# uTrakHF.net
KiCad netlist of a schematic drawn in EAGLE
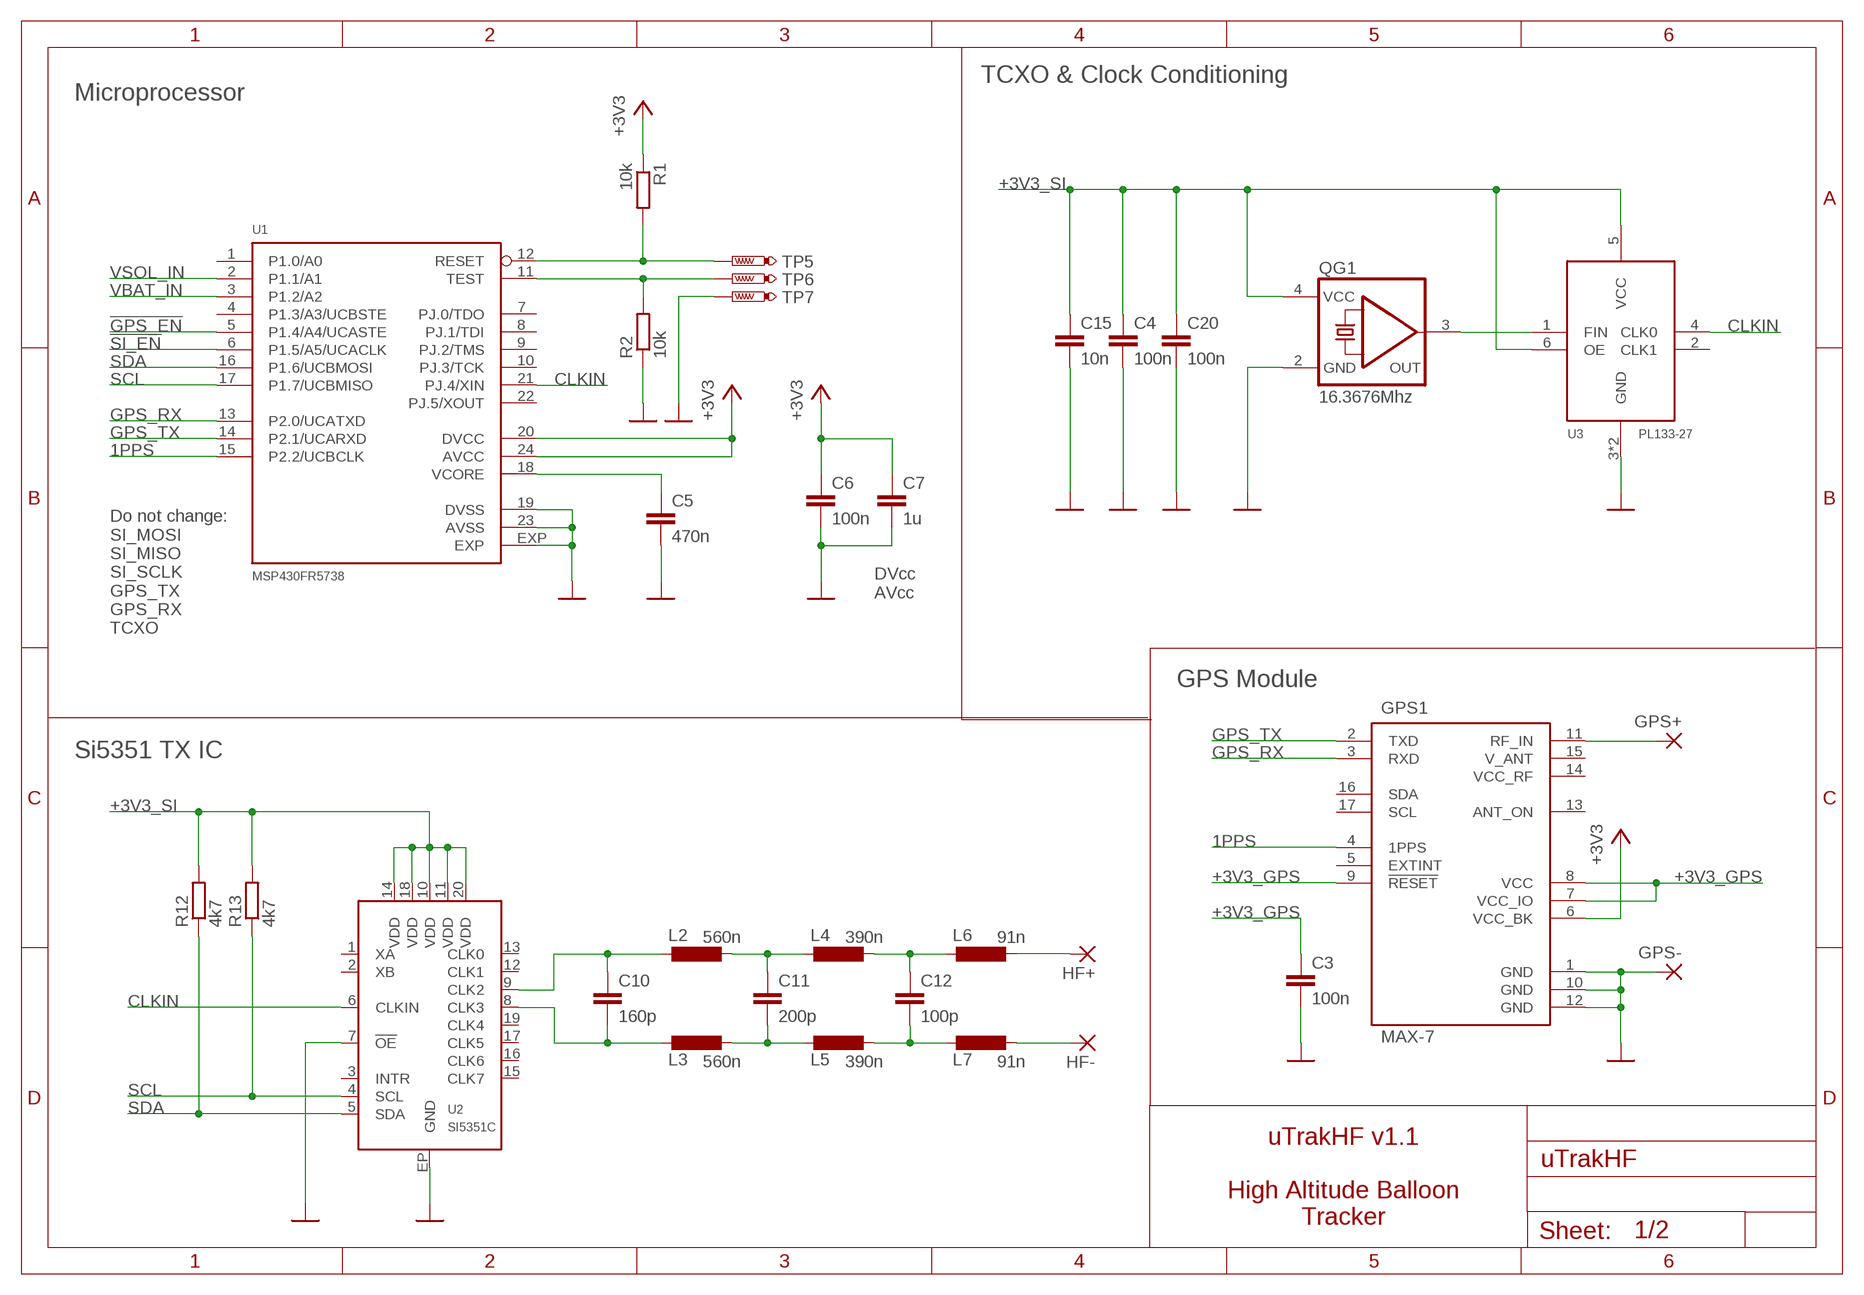
[diagram p0: schematic, sheet 1]
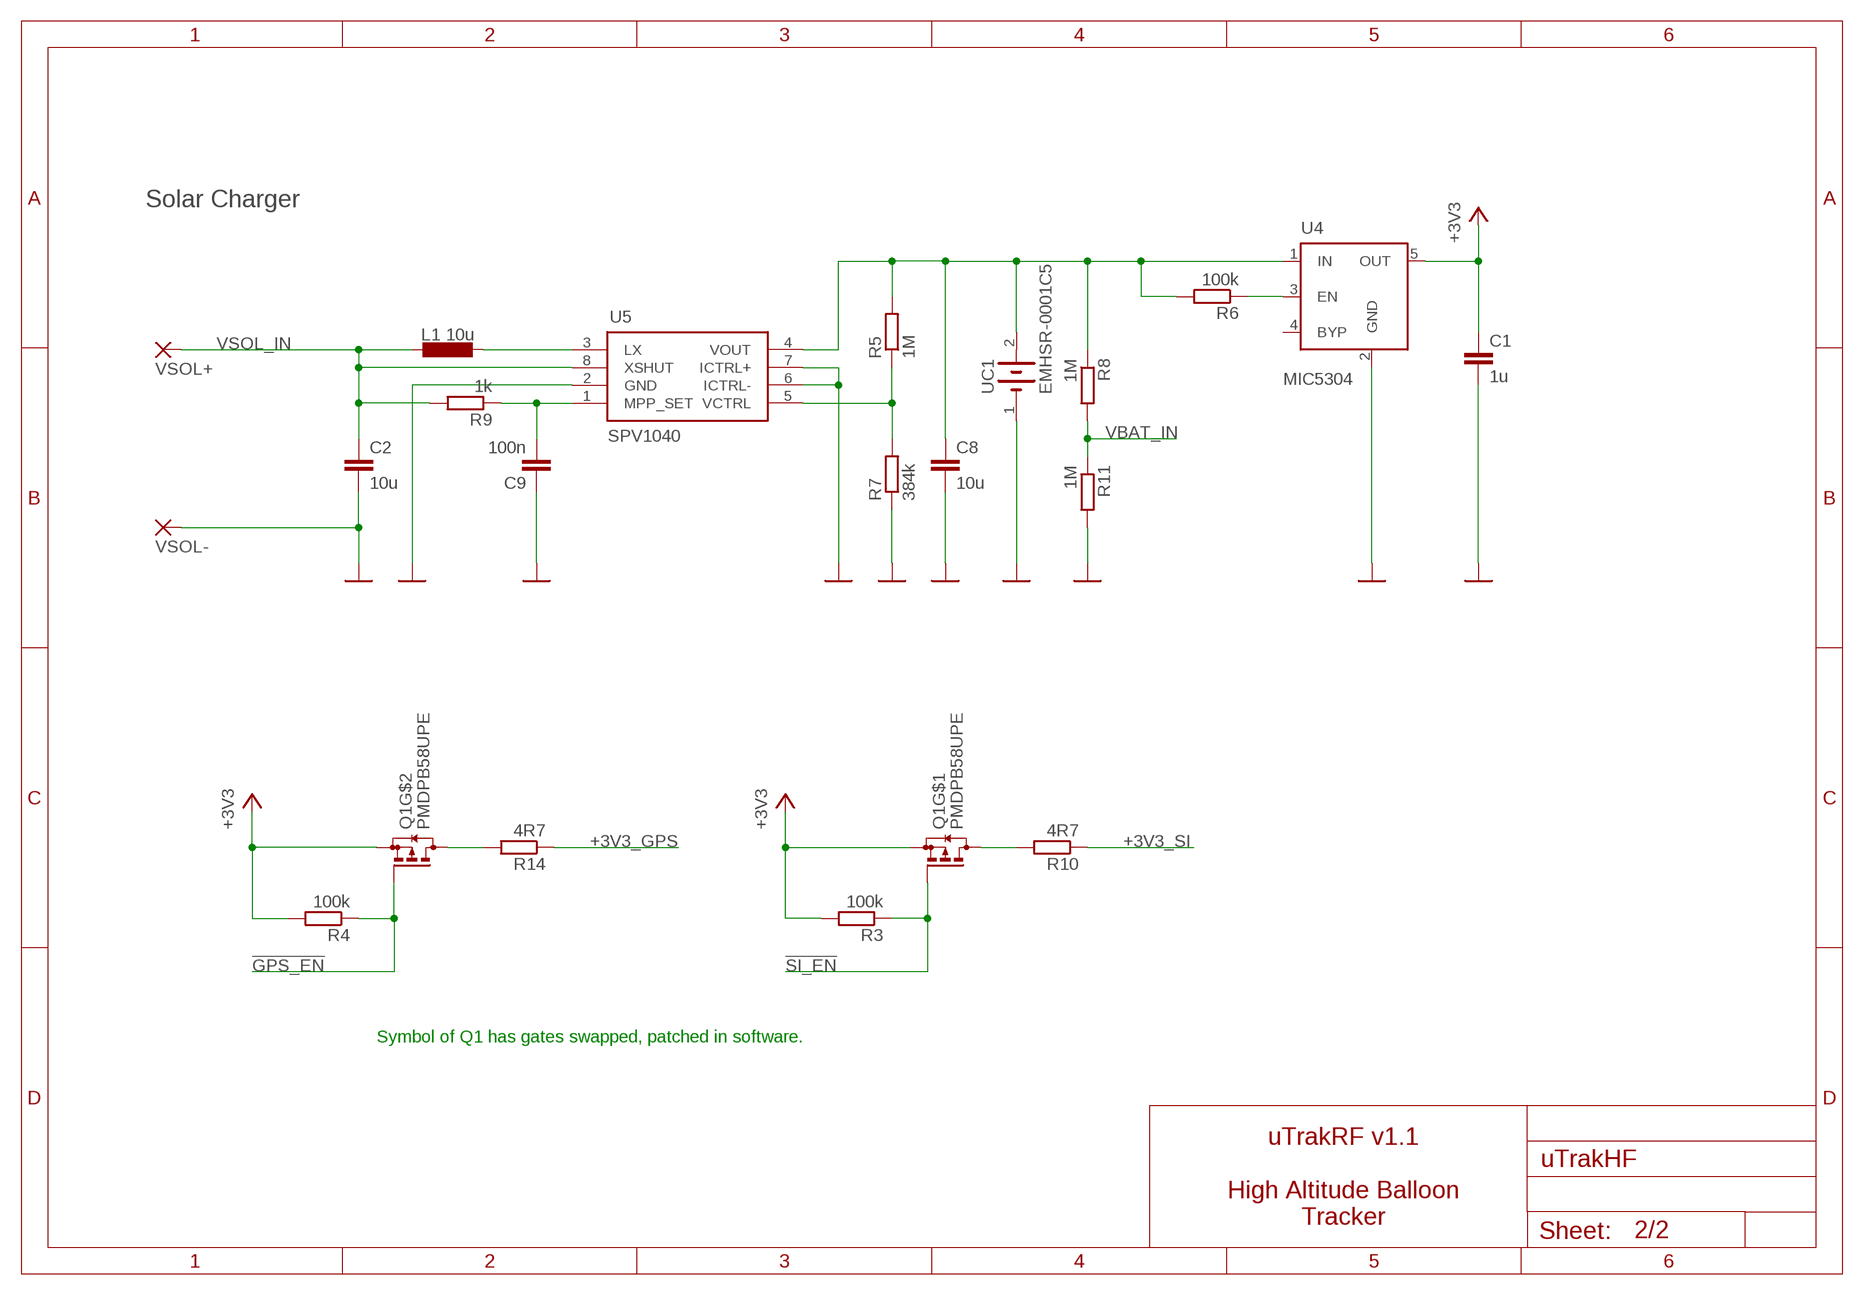
[diagram p1: schematic, sheet 2]

(export (version "E")
  (design (tool "Eeschema 10.0.6"))
  (components
    (comp (ref "C1")
      (value "1u")
      (footprint "eagle-import:C0603")
      (libsource (lib "eagle-import") (part "C-EUC0603"))
    )
    (comp (ref "C2")
      (value "10u")
      (footprint "eagle-import:C0603")
      (libsource (lib "eagle-import") (part "C-EUC0603"))
    )
    (comp (ref "C8")
      (value "10u")
      (footprint "eagle-import:C0603")
      (libsource (lib "eagle-import") (part "C-EUC0603"))
    )
    (comp (ref "C9")
      (value "100n")
      (footprint "eagle-import:C0402")
      (libsource (lib "eagle-import") (part "C-EUC0402"))
    )
    (comp (ref "L1")
      (value "10u")
      (footprint "eagle-import:LPS4018")
      (fields (field (name "PARTNO") "994-LPS4018-223MRB"))
      (libsource (lib "eagle-import") (part "LPS4018"))
    )
    (comp (ref "Q1")
      (value "PMDPB58UPE")
      (footprint "eagle-import:SOT1118")
      (fields (field (name "PARTNO") "771-PMDPB58UPE,115"))
      (libsource (lib "eagle-import") (part "PMDPB58UPE"))
    )
    (comp (ref "R3")
      (value "100k")
      (footprint "eagle-import:R0402")
      (fields (field (name "PARTNO") "603-RC0402FR-07100KL"))
      (libsource (lib "eagle-import") (part "R-EU_R0402"))
    )
    (comp (ref "R4")
      (value "100k")
      (footprint "eagle-import:R0402")
      (fields (field (name "PARTNO") "603-RC0402FR-07100KL"))
      (libsource (lib "eagle-import") (part "R-EU_R0402"))
    )
    (comp (ref "R5")
      (value "1M")
      (footprint "eagle-import:R0402")
      (libsource (lib "eagle-import") (part "R-EU_R0402"))
    )
    (comp (ref "R6")
      (value "100k")
      (footprint "eagle-import:R0402")
      (libsource (lib "eagle-import") (part "R-EU_R0402"))
    )
    (comp (ref "R7")
      (value "384k")
      (footprint "eagle-import:R0402")
      (libsource (lib "eagle-import") (part "R-EU_R0402"))
    )
    (comp (ref "R8")
      (value "1M")
      (footprint "eagle-import:R0402")
      (fields (field (name "PARTNO") "603-RC0402FR-071ML"))
      (libsource (lib "eagle-import") (part "R-EU_R0402"))
    )
    (comp (ref "R9")
      (value "1k")
      (footprint "eagle-import:R0402")
      (libsource (lib "eagle-import") (part "R-EU_R0402"))
    )
    (comp (ref "R10")
      (value "4R7")
      (footprint "eagle-import:R0402")
      (fields (field (name "PARTNO") "603-RC0402FR-07100KL"))
      (libsource (lib "eagle-import") (part "R-EU_R0402"))
    )
    (comp (ref "R11")
      (value "1M")
      (footprint "eagle-import:R0402")
      (fields (field (name "PARTNO") "603-RC0402FR-071ML"))
      (libsource (lib "eagle-import") (part "R-EU_R0402"))
    )
    (comp (ref "R14")
      (value "4R7")
      (footprint "eagle-import:R0402")
      (fields (field (name "PARTNO") "603-RC0402FR-07100KL"))
      (libsource (lib "eagle-import") (part "R-EU_R0402"))
    )
    (comp (ref "U4")
      (value "MIC5304")
      (footprint "eagle-import:SOT23-5")
      (libsource (lib "eagle-import") (part "MIC5219XX"))
    )
    (comp (ref "U5")
      (value "SPV1040")
      (footprint "eagle-import:TSSOP8")
      (libsource (lib "eagle-import") (part "SPV1040"))
    )
    (comp (ref "UC1")
      (value "EMHSR-0001C5")
      (footprint "eagle-import:EMHSR-0001C5-005R0")
      (fields (field (name "PARTNO") "581-SCMR22C155MRBA0"))
      (libsource (lib "eagle-import") (part "EMHSR-0001C5"))
    )
    (comp (ref "VSOL+")
      (value "SMD2")
      (footprint "eagle-import:SMD1,27-2,54")
      (libsource (lib "eagle-import") (part "SMD2"))
    )
    (comp (ref "VSOL-")
      (value "SMD2")
      (footprint "eagle-import:SMD1,27-2,54")
      (libsource (lib "eagle-import") (part "SMD2"))
    )
    (comp (ref "C3")
      (value "100n")
      (footprint "eagle-import:C0402")
      (fields (field (name "PARTNO") "81-GRM155R71C104KA88"))
      (libsource (lib "eagle-import") (part "C-EUC0402"))
    )
    (comp (ref "C4")
      (value "100n")
      (footprint "eagle-import:C0402")
      (fields (field (name "PARTNO") "81-GRM155R71C104KA88"))
      (libsource (lib "eagle-import") (part "C-EUC0402"))
    )
    (comp (ref "C5")
      (value "470n")
      (footprint "eagle-import:C0603")
      (fields (field (name "PARTNO") "81-GCM188R71C474KA5D"))
      (libsource (lib "eagle-import") (part "C-EUC0603"))
    )
    (comp (ref "C6")
      (value "100n")
      (footprint "eagle-import:C0402")
      (fields (field (name "PARTNO") "81-GRM155R71C104KA88"))
      (libsource (lib "eagle-import") (part "C-EUC0402"))
    )
    (comp (ref "C7")
      (value "1u")
      (footprint "eagle-import:C0603")
      (fields (field (name "PARTNO") "81-GRM39R105K10"))
      (libsource (lib "eagle-import") (part "C-EUC0603"))
    )
    (comp (ref "C10")
      (value "160p")
      (footprint "eagle-import:C0402")
      (fields (field (name "PARTNO") "81-GRM1555C1H161JA01"))
      (libsource (lib "eagle-import") (part "C-EUC0402"))
    )
    (comp (ref "C11")
      (value "200p")
      (footprint "eagle-import:C0402")
      (fields (field (name "PARTNO") "81-GRM1555C1H201JA1D"))
      (libsource (lib "eagle-import") (part "C-EUC0402"))
    )
    (comp (ref "C12")
      (value "100p")
      (footprint "eagle-import:C0402")
      (fields (field (name "PARTNO") "81-GRM1555C1H101JA1D"))
      (libsource (lib "eagle-import") (part "C-EUC0402"))
    )
    (comp (ref "C15")
      (value "10n")
      (footprint "eagle-import:C0402")
      (fields (field (name "PARTNO") "81-GRM155R71H103MA8D"))
      (libsource (lib "eagle-import") (part "C-EUC0402"))
    )
    (comp (ref "C20")
      (value "100n")
      (footprint "eagle-import:C0402")
      (fields (field (name "PARTNO") "81-GRM155R71C104KA88"))
      (libsource (lib "eagle-import") (part "C-EUC0402"))
    )
    (comp (ref "GPS+")
      (value "SMD2")
      (footprint "eagle-import:SMD1,27-2,54")
      (libsource (lib "eagle-import") (part "SMD2"))
    )
    (comp (ref "GPS-")
      (value "SMD2")
      (footprint "eagle-import:SMD1,27-2,54")
      (libsource (lib "eagle-import") (part "SMD2"))
    )
    (comp (ref "GPS1")
      (value "MAX-7")
      (footprint "eagle-import:UBLOX-7")
      (libsource (lib "eagle-import") (part "MAX-7"))
    )
    (comp (ref "HF+")
      (value "SMD2")
      (footprint "eagle-import:SMD1,27-2,54")
      (libsource (lib "eagle-import") (part "SMD2"))
    )
    (comp (ref "HF-")
      (value "SMD2")
      (footprint "eagle-import:SMD1,27-2,54")
      (libsource (lib "eagle-import") (part "SMD2"))
    )
    (comp (ref "L2")
      (value "560n")
      (footprint "eagle-import:C0603")
      (fields (field (name "PARTNO") "810-MLJ1608WR56JT000"))
      (libsource (lib "eagle-import") (part "L0603"))
    )
    (comp (ref "L3")
      (value "560n")
      (footprint "eagle-import:C0603")
      (fields (field (name "PARTNO") "810-MLJ1608WR56JT000"))
      (libsource (lib "eagle-import") (part "L0603"))
    )
    (comp (ref "L4")
      (value "390n")
      (footprint "eagle-import:C0603")
      (fields (field (name "PARTNO") "810-MLJ1608WR39JT000"))
      (libsource (lib "eagle-import") (part "L0603"))
    )
    (comp (ref "L5")
      (value "390n")
      (footprint "eagle-import:C0603")
      (fields (field (name "PARTNO") "810-MLJ1608WR39JT000"))
      (libsource (lib "eagle-import") (part "L0603"))
    )
    (comp (ref "L6")
      (value "91n")
      (footprint "eagle-import:C0603")
      (fields (field (name "PARTNO") "81-LQW18AN91NG00D"))
      (libsource (lib "eagle-import") (part "L0603"))
    )
    (comp (ref "L7")
      (value "91n")
      (footprint "eagle-import:C0603")
      (fields (field (name "PARTNO") "81-LQW18AN91NG00D"))
      (libsource (lib "eagle-import") (part "L0603"))
    )
    (comp (ref "QG1")
      (value "16.3676Mhz")
      (footprint "eagle-import:CTS406")
      (libsource (lib "eagle-import") (part "XO"))
    )
    (comp (ref "R1")
      (value "10k")
      (footprint "eagle-import:R0402")
      (fields (field (name "PARTNO") "603-RC0402FR-0710KL"))
      (libsource (lib "eagle-import") (part "R-EU_R0402"))
    )
    (comp (ref "R2")
      (value "10k")
      (footprint "eagle-import:R0402")
      (fields (field (name "PARTNO") "603-RC0402FR-0710KL"))
      (libsource (lib "eagle-import") (part "R-EU_R0402"))
    )
    (comp (ref "R12")
      (value "4k7")
      (footprint "eagle-import:R0402")
      (fields (field (name "PARTNO") "603-RC0402FR-074K7L"))
      (libsource (lib "eagle-import") (part "R-EU_R0402"))
    )
    (comp (ref "R13")
      (value "4k7")
      (footprint "eagle-import:R0402")
      (fields (field (name "PARTNO") "603-RC0402FR-074K7L"))
      (libsource (lib "eagle-import") (part "R-EU_R0402"))
    )
    (comp (ref "TP5")
      (value "PTR1TP10SQ")
      (footprint "eagle-import:TP10SQ")
      (libsource (lib "eagle-import") (part "PTR1TP10SQ"))
    )
    (comp (ref "TP6")
      (value "PTR1TP10SQ")
      (footprint "eagle-import:TP10SQ")
      (libsource (lib "eagle-import") (part "PTR1TP10SQ"))
    )
    (comp (ref "TP7")
      (value "PTR1TP10SQ")
      (footprint "eagle-import:TP10SQ")
      (libsource (lib "eagle-import") (part "PTR1TP10SQ"))
    )
    (comp (ref "U1")
      (value "MSP430FR5738")
      (footprint "eagle-import:QFN24-4X4")
      (fields (field (name "PARTNO") "595-SP430FR5738IRGER"))
      (libsource (lib "eagle-import") (part "MSP430FR5738"))
    )
    (comp (ref "U2")
      (value "SI5351C")
      (footprint "eagle-import:QFN20-4X4")
      (fields (field (name "PARTNO") "634-SI5351C-B-GM"))
      (libsource (lib "eagle-import") (part "SI5351C"))
    )
    (comp (ref "U3")
      (value "PL133-27")
      (footprint "eagle-import:DFN6-2X3")
      (fields (field (name "PARTNO") "998-PL133-27GC-R"))
      (libsource (lib "eagle-import") (part "PL133-27"))
    )
  )
  (nets
    (net (code "1") (name "+3V3") (class "Default")
      (node (ref "C1") (pin "1") (pinfunction "1_1") (pintype "passive"))
      (node (ref "C6") (pin "1") (pinfunction "1_1") (pintype "passive"))
      (node (ref "C7") (pin "1") (pinfunction "1_1") (pintype "passive"))
      (node (ref "GPS1") (pin "6") (pinfunction "VCC_BK_6") (pintype "power_in"))
      (node (ref "Q1") (pin "1") (pinfunction "S_1") (pintype "passive"))
      (node (ref "Q1") (pin "4") (pinfunction "S_4") (pintype "passive"))
      (node (ref "R1") (pin "1") (pinfunction "1_1") (pintype "passive"))
      (node (ref "R3") (pin "2") (pinfunction "2_2") (pintype "passive"))
      (node (ref "R4") (pin "2") (pinfunction "2_2") (pintype "passive"))
      (node (ref "U1") (pin "20") (pinfunction "DVCC_20") (pintype "power_in"))
      (node (ref "U1") (pin "24") (pinfunction "AVCC_24") (pintype "power_in"))
      (node (ref "U4") (pin "5") (pinfunction "OUT_5") (pintype "output"))
    )
    (net (code "2") (name "+3V3_GPS") (class "Default")
      (node (ref "C3") (pin "1") (pinfunction "1_1") (pintype "passive"))
      (node (ref "GPS1") (pin "7") (pinfunction "VCC_IO_7") (pintype "power_in"))
      (node (ref "GPS1") (pin "8") (pinfunction "VCC_8") (pintype "power_in"))
      (node (ref "GPS1") (pin "9") (pinfunction "~{RESET}_9") (pintype "bidirectional"))
      (node (ref "R14") (pin "1") (pinfunction "1_1") (pintype "passive"))
    )
    (net (code "3") (name "+3V3_SI") (class "Default")
      (node (ref "C15") (pin "1") (pinfunction "1_1") (pintype "passive"))
      (node (ref "C20") (pin "1") (pinfunction "1_1") (pintype "passive"))
      (node (ref "C4") (pin "1") (pinfunction "1_1") (pintype "passive"))
      (node (ref "QG1") (pin "4") (pinfunction "VCC_4") (pintype "power_in"))
      (node (ref "R10") (pin "1") (pinfunction "1_1") (pintype "passive"))
      (node (ref "R12") (pin "2") (pinfunction "2_2") (pintype "passive"))
      (node (ref "R13") (pin "2") (pinfunction "2_2") (pintype "passive"))
      (node (ref "U2") (pin "10") (pinfunction "VDD_10") (pintype "bidirectional"))
      (node (ref "U2") (pin "11") (pinfunction "VDD_11") (pintype "bidirectional"))
      (node (ref "U2") (pin "14") (pinfunction "VDD_14") (pintype "bidirectional"))
      (node (ref "U2") (pin "18") (pinfunction "VDD_18") (pintype "bidirectional"))
      (node (ref "U2") (pin "20") (pinfunction "VDD_20") (pintype "bidirectional"))
      (node (ref "U3") (pin "5") (pinfunction "VCC_5") (pintype "power_in"))
      (node (ref "U3") (pin "6") (pinfunction "OE_6") (pintype "bidirectional"))
    )
    (net (code "4") (name "1PPS") (class "Default")
      (node (ref "GPS1") (pin "4") (pinfunction "1PPS_4") (pintype "bidirectional"))
      (node (ref "U1") (pin "15") (pinfunction "P2.2/UCBCLK_15") (pintype "bidirectional"))
    )
    (net (code "5") (name "CLKIN") (class "Default")
      (node (ref "U1") (pin "21") (pinfunction "PJ.4/XIN_21") (pintype "bidirectional"))
      (node (ref "U2") (pin "6") (pinfunction "CLKIN_6") (pintype "bidirectional"))
      (node (ref "U3") (pin "4") (pinfunction "CLK0_4") (pintype "bidirectional"))
    )
    (net (code "6") (name "GND") (class "Default")
      (node (ref "C1") (pin "2") (pinfunction "2_2") (pintype "passive"))
      (node (ref "C15") (pin "2") (pinfunction "2_2") (pintype "passive"))
      (node (ref "C2") (pin "2") (pinfunction "2_2") (pintype "passive"))
      (node (ref "C20") (pin "2") (pinfunction "2_2") (pintype "passive"))
      (node (ref "C3") (pin "2") (pinfunction "2_2") (pintype "passive"))
      (node (ref "C4") (pin "2") (pinfunction "2_2") (pintype "passive"))
      (node (ref "C5") (pin "2") (pinfunction "2_2") (pintype "passive"))
      (node (ref "C6") (pin "2") (pinfunction "2_2") (pintype "passive"))
      (node (ref "C7") (pin "2") (pinfunction "2_2") (pintype "passive"))
      (node (ref "C8") (pin "2") (pinfunction "2_2") (pintype "passive"))
      (node (ref "C9") (pin "1") (pinfunction "1_1") (pintype "passive"))
      (node (ref "GPS-") (pin "1") (pinfunction "P_1") (pintype "passive"))
      (node (ref "GPS1") (pin "1") (pinfunction "GND_1") (pintype "power_in"))
      (node (ref "GPS1") (pin "10") (pinfunction "GND_10") (pintype "power_in"))
      (node (ref "GPS1") (pin "12") (pinfunction "GND_12") (pintype "power_in"))
      (node (ref "QG1") (pin "2") (pinfunction "GND_2") (pintype "power_in"))
      (node (ref "R11") (pin "2") (pinfunction "2_2") (pintype "passive"))
      (node (ref "R2") (pin "1") (pinfunction "1_1") (pintype "passive"))
      (node (ref "R7") (pin "1") (pinfunction "1_1") (pintype "passive"))
      (node (ref "TP7") (pin "TP") (pinfunction "TP_TP") (pintype "input"))
      (node (ref "U1") (pin "19") (pinfunction "DVSS_19") (pintype "power_in"))
      (node (ref "U1") (pin "23") (pinfunction "AVSS_23") (pintype "power_in"))
      (node (ref "U1") (pin "EXP") (pinfunction "EXP_EXP") (pintype "power_in"))
      (node (ref "U2") (pin "7") (pinfunction "~{OE}_7") (pintype "bidirectional"))
      (node (ref "U2") (pin "EP") (pinfunction "GND_EP") (pintype "bidirectional"))
      (node (ref "U3") (pin "3") (pinfunction "GND_3") (pintype "power_in"))
      (node (ref "U3") (pin "EXP") (pinfunction "GND_EXP") (pintype "power_in"))
      (node (ref "U4") (pin "2") (pinfunction "GND_2") (pintype "power_in"))
      (node (ref "U5") (pin "2") (pinfunction "GND_2") (pintype "bidirectional"))
      (node (ref "U5") (pin "6") (pinfunction "ICTRL-_6") (pintype "bidirectional"))
      (node (ref "U5") (pin "7") (pinfunction "ICTRL+_7") (pintype "bidirectional"))
      (node (ref "UC1") (pin "1") (pinfunction "-_1") (pintype "passive"))
      (node (ref "VSOL-") (pin "1") (pinfunction "P_1") (pintype "passive"))
    )
    (net (code "7") (name "GPS_RX") (class "Default")
      (node (ref "GPS1") (pin "3") (pinfunction "RXD_3") (pintype "bidirectional"))
      (node (ref "U1") (pin "13") (pinfunction "P2.0/UCATXD_13") (pintype "bidirectional"))
    )
    (net (code "8") (name "GPS_TX") (class "Default")
      (node (ref "GPS1") (pin "2") (pinfunction "TXD_2") (pintype "bidirectional"))
      (node (ref "U1") (pin "14") (pinfunction "P2.1/UCARXD_14") (pintype "bidirectional"))
    )
    (net (code "9") (name "Net-(C11-Pad1)") (class "Default")
      (node (ref "C11") (pin "1") (pinfunction "1_1") (pintype "passive"))
      (node (ref "L2") (pin "2") (pinfunction "2_2") (pintype "passive"))
      (node (ref "L4") (pin "1") (pinfunction "1_1") (pintype "passive"))
    )
    (net (code "10") (name "Net-(C11-Pad2)") (class "Default")
      (node (ref "C11") (pin "2") (pinfunction "2_2") (pintype "passive"))
      (node (ref "L3") (pin "2") (pinfunction "2_2") (pintype "passive"))
      (node (ref "L5") (pin "1") (pinfunction "1_1") (pintype "passive"))
    )
    (net (code "11") (name "Net-(C12-Pad1)") (class "Default")
      (node (ref "C12") (pin "1") (pinfunction "1_1") (pintype "passive"))
      (node (ref "L4") (pin "2") (pinfunction "2_2") (pintype "passive"))
      (node (ref "L6") (pin "1") (pinfunction "1_1") (pintype "passive"))
    )
    (net (code "12") (name "Net-(C12-Pad2)") (class "Default")
      (node (ref "C12") (pin "2") (pinfunction "2_2") (pintype "passive"))
      (node (ref "L5") (pin "2") (pinfunction "2_2") (pintype "passive"))
      (node (ref "L7") (pin "1") (pinfunction "1_1") (pintype "passive"))
    )
    (net (code "13") (name "Net-(GPS+-P)") (class "Default")
      (node (ref "GPS+") (pin "1") (pinfunction "P_1") (pintype "passive"))
      (node (ref "GPS1") (pin "11") (pinfunction "RF_IN_11") (pintype "bidirectional"))
    )
    (net (code "14") (name "Net-(HF+-P)") (class "Default")
      (node (ref "HF+") (pin "1") (pinfunction "P_1") (pintype "passive"))
      (node (ref "L6") (pin "2") (pinfunction "2_2") (pintype "passive"))
    )
    (net (code "15") (name "Net-(HF--P)") (class "Default")
      (node (ref "HF-") (pin "1") (pinfunction "P_1") (pintype "passive"))
      (node (ref "L7") (pin "2") (pinfunction "2_2") (pintype "passive"))
    )
    (net (code "16") (name "Net-(Q1A-D-Pad3)") (class "Default")
      (node (ref "Q1") (pin "3") (pinfunction "D_3") (pintype "passive"))
      (node (ref "Q1") (pin "8") (pinfunction "D_8") (pintype "passive"))
      (node (ref "R10") (pin "2") (pinfunction "2_2") (pintype "passive"))
    )
    (net (code "17") (name "Net-(Q1B-D-Pad6)") (class "Default")
      (node (ref "Q1") (pin "6") (pinfunction "D_6") (pintype "passive"))
      (node (ref "Q1") (pin "7") (pinfunction "D_7") (pintype "passive"))
      (node (ref "R14") (pin "2") (pinfunction "2_2") (pintype "passive"))
    )
    (net (code "18") (name "Net-(QG1-OUT)") (class "Default")
      (node (ref "QG1") (pin "3") (pinfunction "OUT_3") (pintype "output"))
      (node (ref "U3") (pin "1") (pinfunction "FIN_1") (pintype "bidirectional"))
    )
    (net (code "19") (name "Net-(U1-RESET)") (class "Default")
      (node (ref "R1") (pin "2") (pinfunction "2_2") (pintype "passive"))
      (node (ref "TP5") (pin "TP") (pinfunction "TP_TP") (pintype "input"))
      (node (ref "U1") (pin "12") (pinfunction "RESET_12") (pintype "bidirectional"))
    )
    (net (code "20") (name "Net-(U1-TEST)") (class "Default")
      (node (ref "R2") (pin "2") (pinfunction "2_2") (pintype "passive"))
      (node (ref "TP6") (pin "TP") (pinfunction "TP_TP") (pintype "input"))
      (node (ref "U1") (pin "11") (pinfunction "TEST_11") (pintype "bidirectional"))
    )
    (net (code "21") (name "Net-(U1-VCORE)") (class "Default")
      (node (ref "C5") (pin "1") (pinfunction "1_1") (pintype "passive"))
      (node (ref "U1") (pin "18") (pinfunction "VCORE_18") (pintype "power_in"))
    )
    (net (code "22") (name "Net-(U2-CLK2)") (class "Default")
      (node (ref "C10") (pin "1") (pinfunction "1_1") (pintype "passive"))
      (node (ref "L2") (pin "1") (pinfunction "1_1") (pintype "passive"))
      (node (ref "U2") (pin "9") (pinfunction "CLK2_9") (pintype "bidirectional"))
    )
    (net (code "23") (name "Net-(U2-CLK3)") (class "Default")
      (node (ref "C10") (pin "2") (pinfunction "2_2") (pintype "passive"))
      (node (ref "L3") (pin "1") (pinfunction "1_1") (pintype "passive"))
      (node (ref "U2") (pin "8") (pinfunction "CLK3_8") (pintype "bidirectional"))
    )
    (net (code "24") (name "Net-(U4-EN)") (class "Default")
      (node (ref "R6") (pin "1") (pinfunction "1_1") (pintype "passive"))
      (node (ref "U4") (pin "3") (pinfunction "EN_3") (pintype "input"))
    )
    (net (code "25") (name "Net-(U4-IN)") (class "Default")
      (node (ref "C8") (pin "1") (pinfunction "1_1") (pintype "passive"))
      (node (ref "R5") (pin "2") (pinfunction "2_2") (pintype "passive"))
      (node (ref "R6") (pin "2") (pinfunction "2_2") (pintype "passive"))
      (node (ref "R8") (pin "1") (pinfunction "1_1") (pintype "passive"))
      (node (ref "U4") (pin "1") (pinfunction "IN_1") (pintype "input"))
      (node (ref "U5") (pin "4") (pinfunction "VOUT_4") (pintype "bidirectional"))
      (node (ref "UC1") (pin "2") (pinfunction "+_2") (pintype "passive"))
    )
    (net (code "26") (name "Net-(U5-LX)") (class "Default")
      (node (ref "L1") (pin "1") (pinfunction "1_1") (pintype "passive"))
      (node (ref "U5") (pin "3") (pinfunction "LX_3") (pintype "bidirectional"))
    )
    (net (code "27") (name "Net-(U5-MPP_SET)") (class "Default")
      (node (ref "C9") (pin "2") (pinfunction "2_2") (pintype "passive"))
      (node (ref "R9") (pin "1") (pinfunction "1_1") (pintype "passive"))
      (node (ref "U5") (pin "1") (pinfunction "MPP_SET_1") (pintype "bidirectional"))
    )
    (net (code "28") (name "Net-(U5-VCTRL)") (class "Default")
      (node (ref "R5") (pin "1") (pinfunction "1_1") (pintype "passive"))
      (node (ref "R7") (pin "2") (pinfunction "2_2") (pintype "passive"))
      (node (ref "U5") (pin "5") (pinfunction "VCTRL_5") (pintype "bidirectional"))
    )
    (net (code "29") (name "SCL") (class "Default")
      (node (ref "R13") (pin "1") (pinfunction "1_1") (pintype "passive"))
      (node (ref "U1") (pin "17") (pinfunction "P1.7/UCBMISO_17") (pintype "bidirectional"))
      (node (ref "U2") (pin "4") (pinfunction "SCL_4") (pintype "bidirectional"))
    )
    (net (code "30") (name "SDA") (class "Default")
      (node (ref "R12") (pin "1") (pinfunction "1_1") (pintype "passive"))
      (node (ref "U1") (pin "16") (pinfunction "P1.6/UCBMOSI_16") (pintype "bidirectional"))
      (node (ref "U2") (pin "5") (pinfunction "SDA_5") (pintype "bidirectional"))
    )
    (net (code "31") (name "VBAT_IN") (class "Default")
      (node (ref "R11") (pin "1") (pinfunction "1_1") (pintype "passive"))
      (node (ref "R8") (pin "2") (pinfunction "2_2") (pintype "passive"))
      (node (ref "U1") (pin "3") (pinfunction "P1.2/A2_3") (pintype "bidirectional"))
    )
    (net (code "32") (name "VSOL_IN") (class "Default")
      (node (ref "C2") (pin "1") (pinfunction "1_1") (pintype "passive"))
      (node (ref "L1") (pin "2") (pinfunction "2_2") (pintype "passive"))
      (node (ref "R9") (pin "2") (pinfunction "2_2") (pintype "passive"))
      (node (ref "U1") (pin "2") (pinfunction "P1.1/A1_2") (pintype "bidirectional"))
      (node (ref "U5") (pin "8") (pinfunction "XSHUT_8") (pintype "bidirectional"))
      (node (ref "VSOL+") (pin "1") (pinfunction "P_1") (pintype "passive"))
    )
    (net (code "33") (name "unconnected-(GPS1-ANT_ON-Pad13)") (class "Default")
      (node (ref "GPS1") (pin "13") (pinfunction "ANT_ON_13") (pintype "bidirectional"))
    )
    (net (code "34") (name "unconnected-(GPS1-EXTINT-Pad5)") (class "Default")
      (node (ref "GPS1") (pin "5") (pinfunction "EXTINT_5") (pintype "bidirectional"))
    )
    (net (code "35") (name "unconnected-(GPS1-SCL-Pad17)") (class "Default")
      (node (ref "GPS1") (pin "17") (pinfunction "SCL_17") (pintype "bidirectional"))
    )
    (net (code "36") (name "unconnected-(GPS1-SDA-Pad16)") (class "Default")
      (node (ref "GPS1") (pin "16") (pinfunction "SDA_16") (pintype "bidirectional"))
    )
    (net (code "37") (name "unconnected-(GPS1-VCC_RF-Pad14)") (class "Default")
      (node (ref "GPS1") (pin "14") (pinfunction "VCC_RF_14") (pintype "bidirectional"))
    )
    (net (code "38") (name "unconnected-(GPS1-V_ANT-Pad15)") (class "Default")
      (node (ref "GPS1") (pin "15") (pinfunction "V_ANT_15") (pintype "bidirectional"))
    )
    (net (code "39") (name "unconnected-(U1-P1.0{slash}A0-Pad1)") (class "Default")
      (node (ref "U1") (pin "1") (pinfunction "P1.0/A0_1") (pintype "bidirectional"))
    )
    (net (code "40") (name "unconnected-(U1-P1.3{slash}A3{slash}UCBSTE-Pad4)") (class "Default")
      (node (ref "U1") (pin "4") (pinfunction "P1.3/A3/UCBSTE_4") (pintype "bidirectional"))
    )
    (net (code "41") (name "unconnected-(U1-PJ.0{slash}TDO-Pad7)") (class "Default")
      (node (ref "U1") (pin "7") (pinfunction "PJ.0/TDO_7") (pintype "bidirectional"))
    )
    (net (code "42") (name "unconnected-(U1-PJ.1{slash}TDI-Pad8)") (class "Default")
      (node (ref "U1") (pin "8") (pinfunction "PJ.1/TDI_8") (pintype "bidirectional"))
    )
    (net (code "43") (name "unconnected-(U1-PJ.2{slash}TMS-Pad9)") (class "Default")
      (node (ref "U1") (pin "9") (pinfunction "PJ.2/TMS_9") (pintype "bidirectional"))
    )
    (net (code "44") (name "unconnected-(U1-PJ.3{slash}TCK-Pad10)") (class "Default")
      (node (ref "U1") (pin "10") (pinfunction "PJ.3/TCK_10") (pintype "bidirectional"))
    )
    (net (code "45") (name "unconnected-(U1-PJ.5{slash}XOUT-Pad22)") (class "Default")
      (node (ref "U1") (pin "22") (pinfunction "PJ.5/XOUT_22") (pintype "bidirectional"))
    )
    (net (code "46") (name "unconnected-(U2-CLK0-Pad13)") (class "Default")
      (node (ref "U2") (pin "13") (pinfunction "CLK0_13") (pintype "bidirectional"))
    )
    (net (code "47") (name "unconnected-(U2-CLK1-Pad12)") (class "Default")
      (node (ref "U2") (pin "12") (pinfunction "CLK1_12") (pintype "bidirectional"))
    )
    (net (code "48") (name "unconnected-(U2-CLK4-Pad19)") (class "Default")
      (node (ref "U2") (pin "19") (pinfunction "CLK4_19") (pintype "bidirectional"))
    )
    (net (code "49") (name "unconnected-(U2-CLK5-Pad17)") (class "Default")
      (node (ref "U2") (pin "17") (pinfunction "CLK5_17") (pintype "bidirectional"))
    )
    (net (code "50") (name "unconnected-(U2-CLK6-Pad16)") (class "Default")
      (node (ref "U2") (pin "16") (pinfunction "CLK6_16") (pintype "bidirectional"))
    )
    (net (code "51") (name "unconnected-(U2-CLK7-Pad15)") (class "Default")
      (node (ref "U2") (pin "15") (pinfunction "CLK7_15") (pintype "bidirectional"))
    )
    (net (code "52") (name "unconnected-(U2-INTR-Pad3)") (class "Default")
      (node (ref "U2") (pin "3") (pinfunction "INTR_3") (pintype "bidirectional"))
    )
    (net (code "53") (name "unconnected-(U2-XA-Pad1)") (class "Default")
      (node (ref "U2") (pin "1") (pinfunction "XA_1") (pintype "bidirectional"))
    )
    (net (code "54") (name "unconnected-(U2-XB-Pad2)") (class "Default")
      (node (ref "U2") (pin "2") (pinfunction "XB_2") (pintype "bidirectional"))
    )
    (net (code "55") (name "unconnected-(U3-CLK1-Pad2)") (class "Default")
      (node (ref "U3") (pin "2") (pinfunction "CLK1_2") (pintype "bidirectional"))
    )
    (net (code "56") (name "unconnected-(U4-BYP-Pad4)") (class "Default")
      (node (ref "U4") (pin "4") (pinfunction "BYP_4") (pintype "passive"))
    )
    (net (code "57") (name "~{GPS_EN}") (class "Default")
      (node (ref "Q1") (pin "5") (pinfunction "G_5") (pintype "passive"))
      (node (ref "R4") (pin "1") (pinfunction "1_1") (pintype "passive"))
      (node (ref "U1") (pin "5") (pinfunction "P1.4/A4/UCASTE_5") (pintype "bidirectional"))
    )
    (net (code "58") (name "~{SI_EN}") (class "Default")
      (node (ref "Q1") (pin "2") (pinfunction "G_2") (pintype "passive"))
      (node (ref "R3") (pin "1") (pinfunction "1_1") (pintype "passive"))
      (node (ref "U1") (pin "6") (pinfunction "P1.5/A5/UCACLK_6") (pintype "bidirectional"))
    )
  )
)
